# power.net
KiCad netlist of a schematic drawn in Altium Designer
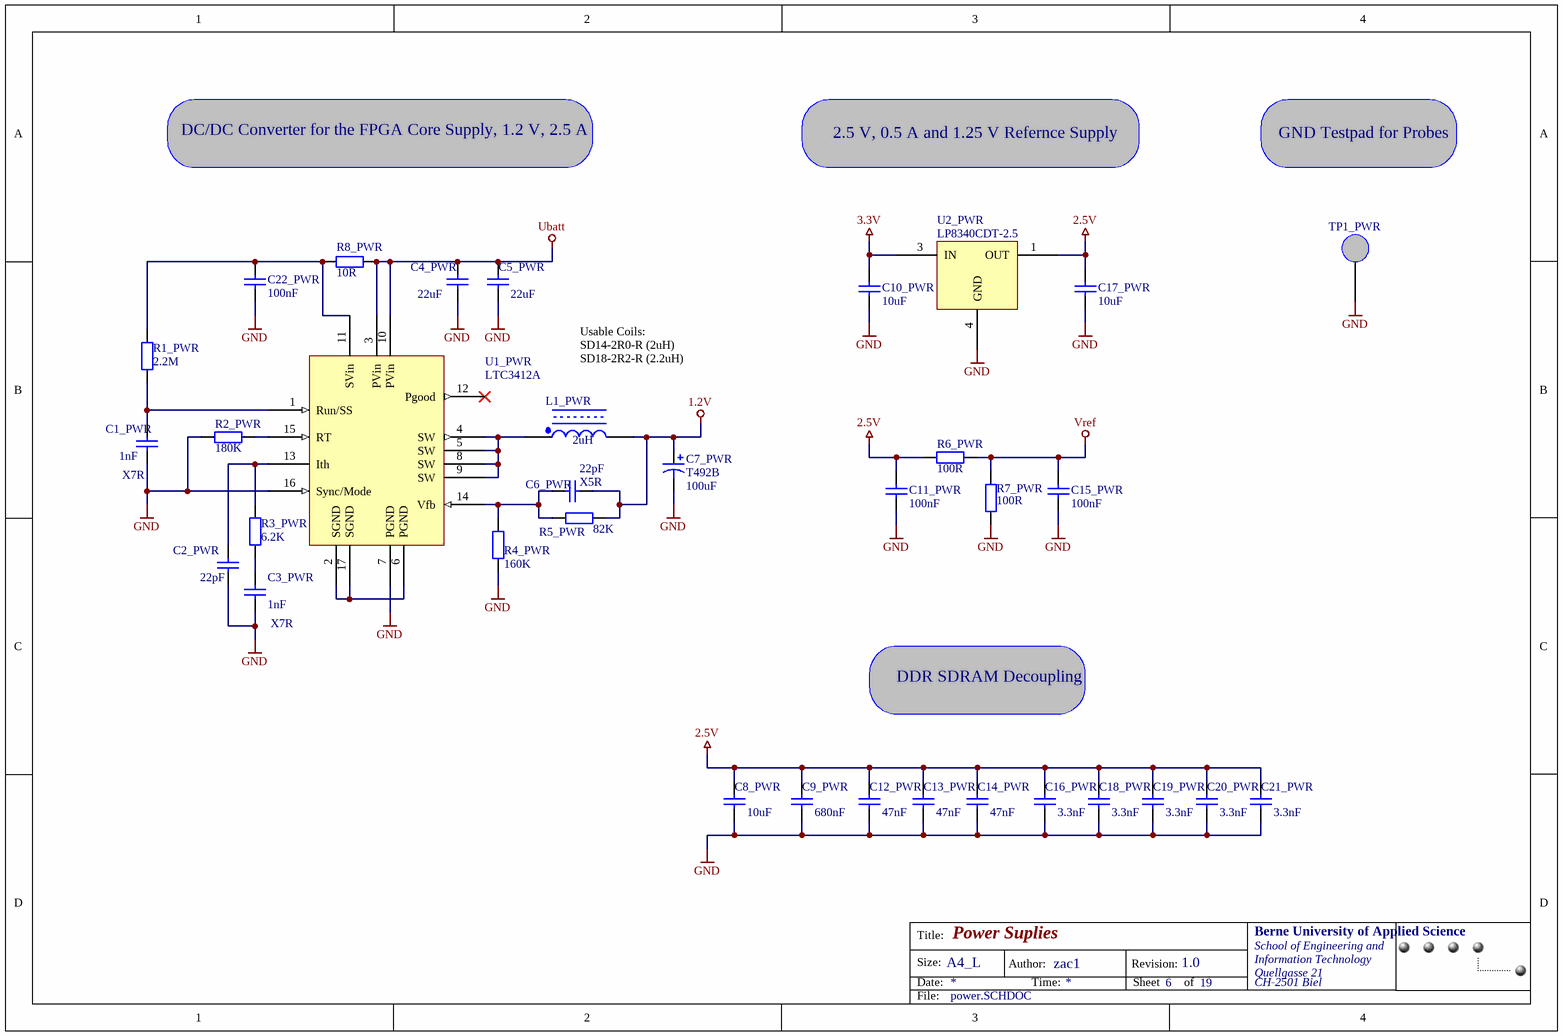
[diagram p0: power.SCHDOC]

(export (version "E")
  (design (tool "Eeschema 10.0.6"))
  (components
    (comp (ref "C1_PWR")
      (value "1nF")
      (footprint "0402")
      (description "Capacitor")
      (fields
        (field (name "MANUFACTURER") "PHYCOMP")
        (field (name "SPEC") "X7R")
        (field (name "PART NUMBER") "2238 587 15623")
        (field (name "PUBLISHER") "Altium Limited")
      )
      (libsource (lib "Miscellaneous Devices") (part "Cap"))
    )
    (comp (ref "C2_PWR")
      (value "22pF")
      (footprint "0402")
      (description "Capacitor")
      (fields
        (field (name "MANUFACTURER") "Murata")
        (field (name "PART NUMBER") "GRM1555C1H220JZ01D")
        (field (name "PUBLISHER") "Altium Limited")
      )
      (libsource (lib "Miscellaneous Devices") (part "Cap"))
    )
    (comp (ref "C3_PWR")
      (value "1nF")
      (footprint "0402")
      (description "Capacitor")
      (fields
        (field (name "MANUFACTURER") "PHYCOMP")
        (field (name "SPEC") "X7R")
        (field (name "PART NUMBER") "2238 587 15623")
        (field (name "PUBLISHER") "Altium Limited")
      )
      (libsource (lib "Miscellaneous Devices") (part "Cap"))
    )
    (comp (ref "C4_PWR")
      (value "22uF")
      (footprint "CC3225-1210")
      (description "Capacitor")
      (fields
        (field (name "MANUFACTURER") "Yuden")
        (field (name "PART NUMBER") "EMK325BJ226MM-T")
        (field (name "PUBLISHER") "Altium Limited")
      )
      (libsource (lib "Miscellaneous Devices") (part "Cap"))
    )
    (comp (ref "C5_PWR")
      (value "22uF")
      (footprint "1210")
      (description "Capacitor")
      (fields
        (field (name "MANUFACTURER") "Yuden")
        (field (name "PART NUMBER") "EMK325BJ226MM-T")
        (field (name "PUBLISHER") "Altium Limited")
      )
      (libsource (lib "Miscellaneous Devices") (part "Cap"))
    )
    (comp (ref "C6_PWR")
      (value "22pF")
      (footprint "0402")
      (description "Capacitor")
      (fields
        (field (name "MANUFACTURER") "Murata")
        (field (name "SPEC") "X5R")
        (field (name "PART NUMBER") "GRM1555C1H220JZ01D")
        (field (name "PUBLISHER") "Altium Limited")
      )
      (libsource (lib "Miscellaneous Devices") (part "Cap"))
    )
    (comp (ref "C7_PWR")
      (value "T492B")
      (footprint "B")
      (description "Solid Tantalum Chip Capacitor, T492 Series - CWR11 Style Per Mil-PRF-55365/8")
      (fields
        (field (name "ALTIUM_VALUE") "100uF")
        (field (name "MANUFACTURER") "AVX")
        (field (name "PART NUMBER") "TCJB107M004R0070")
        (field (name "PUBLISHER") "Altium Limited")
      )
      (libsource (lib "KEMET Chip Capacitor") (part "T492B"))
    )
    (comp (ref "C8_PWR")
      (value "10uF")
      (footprint "1206")
      (description "Capacitor")
      (fields
        (field (name "MANUFACTURER") "Murata")
        (field (name "PART NUMBER") "GRM31CR70J106KA01L")
        (field (name "PUBLISHER") "Altium Limited")
      )
      (libsource (lib "Miscellaneous Devices") (part "Cap"))
    )
    (comp (ref "C9_PWR")
      (value "680nF")
      (footprint "0805")
      (description "Capacitor")
      (fields
        (field (name "MANUFACTURER") "PHYCOMP")
        (field (name "PART NUMBER") "2238 240 15661")
        (field (name "PUBLISHER") "Altium Limited")
      )
      (libsource (lib "Miscellaneous Devices") (part "Cap"))
    )
    (comp (ref "C10_PWR")
      (value "10uF")
      (footprint "1206")
      (description "Capacitor")
      (fields
        (field (name "MANUFACTURER") "Murata")
        (field (name "PART NUMBER") "GRM31CR70J106KA01L")
        (field (name "PUBLISHER") "Altium Limited")
      )
      (libsource (lib "Miscellaneous Devices") (part "Cap"))
    )
    (comp (ref "C11_PWR")
      (value "100nF")
      (footprint "0402")
      (description "Capacitor")
      (fields
        (field (name "MANUFACTURER") "Murata")
        (field (name "PART NUMBER") "GRM155R71C104KA88D")
        (field (name "PUBLISHER") "Altium Limited")
      )
      (libsource (lib "Miscellaneous Devices") (part "Cap"))
    )
    (comp (ref "C12_PWR")
      (value "47nF")
      (footprint "0402")
      (description "Capacitor")
      (fields
        (field (name "MANUFACTURER") "PHYCOMP")
        (field (name "PART NUMBER") "2238 787 19845")
        (field (name "PUBLISHER") "Altium Limited")
      )
      (libsource (lib "Miscellaneous Devices") (part "Cap"))
    )
    (comp (ref "C13_PWR")
      (value "47nF")
      (footprint "0402")
      (description "Capacitor")
      (fields
        (field (name "MANUFACTURER") "PHYCOMP")
        (field (name "PART NUMBER") "2238 787 19845")
        (field (name "PUBLISHER") "Altium Limited")
      )
      (libsource (lib "Miscellaneous Devices") (part "Cap"))
    )
    (comp (ref "C14_PWR")
      (value "47nF")
      (footprint "0402")
      (description "Capacitor")
      (fields
        (field (name "MANUFACTURER") "PHYCOMP")
        (field (name "PART NUMBER") "2238 787 19845")
        (field (name "PUBLISHER") "Altium Limited")
      )
      (libsource (lib "Miscellaneous Devices") (part "Cap"))
    )
    (comp (ref "C15_PWR")
      (value "100nF")
      (footprint "0402")
      (description "Capacitor")
      (fields
        (field (name "MANUFACTURER") "Murata")
        (field (name "PART NUMBER") "GRM155R71C104KA88D")
        (field (name "PUBLISHER") "Altium Limited")
      )
      (libsource (lib "Miscellaneous Devices") (part "Cap"))
    )
    (comp (ref "C16_PWR")
      (value "3.3nF")
      (footprint "0402")
      (description "Capacitor")
      (fields
        (field (name "MANUFACTURER") "PHYCOMP")
        (field (name "PART NUMBER") "2238 587 15629")
        (field (name "PUBLISHER") "Altium Limited")
      )
      (libsource (lib "Miscellaneous Devices") (part "Cap"))
    )
    (comp (ref "C17_PWR")
      (value "10uF")
      (footprint "1206")
      (description "Capacitor")
      (fields
        (field (name "MANUFACTURER") "Murata")
        (field (name "PART NUMBER") "GRM31CR70J106KA01L")
        (field (name "PUBLISHER") "Altium Limited")
      )
      (libsource (lib "Miscellaneous Devices") (part "Cap"))
    )
    (comp (ref "C18_PWR")
      (value "3.3nF")
      (footprint "0402")
      (description "Capacitor")
      (fields
        (field (name "MANUFACTURER") "PHYCOMP")
        (field (name "PART NUMBER") "2238 587 15629")
        (field (name "PUBLISHER") "Altium Limited")
      )
      (libsource (lib "Miscellaneous Devices") (part "Cap"))
    )
    (comp (ref "C19_PWR")
      (value "3.3nF")
      (footprint "0402")
      (description "Capacitor")
      (fields
        (field (name "MANUFACTURER") "PHYCOMP")
        (field (name "PART NUMBER") "2238 587 15629")
        (field (name "PUBLISHER") "Altium Limited")
      )
      (libsource (lib "Miscellaneous Devices") (part "Cap"))
    )
    (comp (ref "C20_PWR")
      (value "3.3nF")
      (footprint "0402")
      (description "Capacitor")
      (fields
        (field (name "MANUFACTURER") "PHYCOMP")
        (field (name "PART NUMBER") "2238 587 15629")
        (field (name "PUBLISHER") "Altium Limited")
      )
      (libsource (lib "Miscellaneous Devices") (part "Cap"))
    )
    (comp (ref "C21_PWR")
      (value "3.3nF")
      (footprint "0402")
      (description "Capacitor")
      (fields
        (field (name "MANUFACTURER") "PHYCOMP")
        (field (name "PART NUMBER") "2238 587 15629")
        (field (name "PUBLISHER") "Altium Limited")
      )
      (libsource (lib "Miscellaneous Devices") (part "Cap"))
    )
    (comp (ref "C22_PWR")
      (value "100nF")
      (footprint "0402")
      (description "Capacitor")
      (fields
        (field (name "MANUFACTURER") "Murata")
        (field (name "PART NUMBER") "GRM155R71C104KA88D")
        (field (name "PUBLISHER") "Altium Limited")
      )
      (libsource (lib "") (part "Cap_1"))
    )
    (comp (ref "L1_PWR")
      (value "2uH")
      (footprint "coil-sd-serie")
      (description "SD Series Coils from Coiltronics")
      (fields (field (name "MANUFACTURER") "Cooper Bussmann") (field (name "PART NUMBER") "SD14-2R0-R"))
      (libsource (lib "gecko3-user") (part "COIL-SD-SERIE"))
    )
    (comp (ref "R1_PWR")
      (value "2.2M")
      (footprint "0402")
      (description "Resistor")
      (fields
        (field (name "MANUFACTURER") "PHYCOMP")
        (field (name "PART NUMBER") "232270672205")
        (field (name "PUBLISHER") "Altium Limited")
      )
      (libsource (lib "Miscellaneous Devices") (part "Res2"))
    )
    (comp (ref "R2_PWR")
      (value "180K")
      (footprint "0402")
      (description "Resistor")
      (fields
        (field (name "MANUFACTURER") "PHYCOMP")
        (field (name "PART NUMBER") "232270671804")
        (field (name "PUBLISHER") "Altium Limited")
      )
      (libsource (lib "") (part "Res2_1"))
    )
    (comp (ref "R3_PWR")
      (value "6.2K")
      (footprint "0603")
      (description "Resistor")
      (fields
        (field (name "MANUFACTURER") "Multicomp")
        (field (name "PART NUMBER") "MC 0.063W 0603 1% 6K2")
        (field (name "PUBLISHER") "Altium Limited")
      )
      (libsource (lib "") (part "Res2_2"))
    )
    (comp (ref "R4_PWR")
      (value "160K")
      (footprint "0603")
      (description "Resistor")
      (fields
        (field (name "MANUFACTURER") "Multicomp")
        (field (name "PART NUMBER") "MC 0.063W 0603 1% 160K")
        (field (name "PUBLISHER") "Altium Limited")
      )
      (libsource (lib "Miscellaneous Devices") (part "Res2"))
    )
    (comp (ref "R5_PWR")
      (value "82K")
      (footprint "0402")
      (description "Resistor")
      (fields
        (field (name "MANUFACTURER") "PHYCOMP")
        (field (name "PART NUMBER") "232270678203")
        (field (name "PUBLISHER") "Altium Limited")
      )
      (libsource (lib "") (part "Res2_1"))
    )
    (comp (ref "R6_PWR")
      (value "100R")
      (footprint "0402")
      (description "Resistor")
      (fields
        (field (name "MANUFACTURER") "PHYCOMP")
        (field (name "PART NUMBER") "232270671001")
        (field (name "PUBLISHER") "Altium Limited")
      )
      (libsource (lib "") (part "Res2_1"))
    )
    (comp (ref "R7_PWR")
      (value "100R")
      (footprint "0402")
      (description "Resistor")
      (fields
        (field (name "MANUFACTURER") "PHYCOMP")
        (field (name "PART NUMBER") "232270671001")
        (field (name "PUBLISHER") "Altium Limited")
      )
      (libsource (lib "Miscellaneous Devices") (part "Res2"))
    )
    (comp (ref "R8_PWR")
      (value "10R")
      (footprint "0402")
      (description "Resistor")
      (fields
        (field (name "MANUFACTURER") "TYCO ELECTRONICS")
        (field (name "PART NUMBER") "CRG0402J10R-10")
        (field (name "PUBLISHER") "Altium Limited")
      )
      (libsource (lib "") (part "Res2_1"))
    )
    (comp (ref "TP1_PWR")
      (value "TESTPAD-SMD")
      (footprint "TESTPAD-SMD")
      (description "Harwin SMD Testpad")
      (fields (field (name "MANUFACTURER") "HARWIN") (field (name "PART NUMBER") "S1751-46R"))
      (libsource (lib "gecko3-user") (part "TESTPAD-SMD"))
    )
    (comp (ref "U1_PWR")
      (value "LTC3412A")
      (footprint "QFN16")
      (description "3 A, 4 MHz, Step-Down Regulator")
      (fields (field (name "MANUFACTURER") "Linear") (field (name "PART NUMBER") "LTC3412AEUF#PBF"))
      (libsource (lib "gecko3-user") (part "LTC3412A"))
    )
    (comp (ref "U2_PWR")
      (value "LP8340CDT-2.5")
      (footprint "TO-252")
      (description "Low Dropout, Low IQ, 1.0A CMOS Linear Regulator")
      (fields (field (name "MANUFACTURER") "National") (field (name "Comment") "LP8340CDT"))
      (libsource (lib "gecko3-user") (part "LP8340CDT"))
    )
  )
  (nets
    (net (code "1") (name "1.2V") (class "Default")
      (node (ref "C6_PWR") (pin "1") (pinfunction "1_1") (pintype "passive"))
      (node (ref "C7_PWR") (pin "1") (pinfunction "1_1") (pintype "passive"))
      (node (ref "L1_PWR") (pin "2") (pinfunction "2_2") (pintype "passive"))
      (node (ref "R5_PWR") (pin "1") (pinfunction "1_1") (pintype "passive"))
    )
    (net (code "2") (name "2.5V") (class "Default")
      (node (ref "C11_PWR") (pin "2") (pinfunction "2_2") (pintype "passive"))
      (node (ref "C12_PWR") (pin "1") (pinfunction "1_1") (pintype "passive"))
      (node (ref "C13_PWR") (pin "1") (pinfunction "1_1") (pintype "passive"))
      (node (ref "C14_PWR") (pin "1") (pinfunction "1_1") (pintype "passive"))
      (node (ref "C16_PWR") (pin "1") (pinfunction "1_1") (pintype "passive"))
      (node (ref "C17_PWR") (pin "2") (pinfunction "2_2") (pintype "passive"))
      (node (ref "C18_PWR") (pin "1") (pinfunction "1_1") (pintype "passive"))
      (node (ref "C19_PWR") (pin "1") (pinfunction "1_1") (pintype "passive"))
      (node (ref "C20_PWR") (pin "1") (pinfunction "1_1") (pintype "passive"))
      (node (ref "C21_PWR") (pin "1") (pinfunction "1_1") (pintype "passive"))
      (node (ref "C8_PWR") (pin "1") (pinfunction "1_1") (pintype "passive"))
      (node (ref "C9_PWR") (pin "1") (pinfunction "1_1") (pintype "passive"))
      (node (ref "R6_PWR") (pin "2") (pinfunction "2_2") (pintype "passive"))
      (node (ref "U2_PWR") (pin "1") (pinfunction "OUT_1") (pintype "power_in"))
    )
    (net (code "3") (name "3.3V") (class "Default")
      (node (ref "C10_PWR") (pin "2") (pinfunction "2_2") (pintype "passive"))
      (node (ref "U2_PWR") (pin "3") (pinfunction "IN_3") (pintype "power_in"))
    )
    (net (code "4") (name "GND") (class "Default")
      (node (ref "C10_PWR") (pin "1") (pinfunction "1_1") (pintype "passive"))
      (node (ref "C11_PWR") (pin "1") (pinfunction "1_1") (pintype "passive"))
      (node (ref "C12_PWR") (pin "2") (pinfunction "2_2") (pintype "passive"))
      (node (ref "C13_PWR") (pin "2") (pinfunction "2_2") (pintype "passive"))
      (node (ref "C14_PWR") (pin "2") (pinfunction "2_2") (pintype "passive"))
      (node (ref "C15_PWR") (pin "1") (pinfunction "1_1") (pintype "passive"))
      (node (ref "C16_PWR") (pin "2") (pinfunction "2_2") (pintype "passive"))
      (node (ref "C17_PWR") (pin "1") (pinfunction "1_1") (pintype "passive"))
      (node (ref "C18_PWR") (pin "2") (pinfunction "2_2") (pintype "passive"))
      (node (ref "C19_PWR") (pin "2") (pinfunction "2_2") (pintype "passive"))
      (node (ref "C1_PWR") (pin "1") (pinfunction "1_1") (pintype "passive"))
      (node (ref "C20_PWR") (pin "2") (pinfunction "2_2") (pintype "passive"))
      (node (ref "C21_PWR") (pin "2") (pinfunction "2_2") (pintype "passive"))
      (node (ref "C22_PWR") (pin "2") (pinfunction "2_2") (pintype "passive"))
      (node (ref "C2_PWR") (pin "1") (pinfunction "1_1") (pintype "passive"))
      (node (ref "C3_PWR") (pin "1") (pinfunction "1_1") (pintype "passive"))
      (node (ref "C4_PWR") (pin "1") (pinfunction "1_1") (pintype "passive"))
      (node (ref "C5_PWR") (pin "1") (pinfunction "1_1") (pintype "passive"))
      (node (ref "C7_PWR") (pin "2") (pinfunction "2_2") (pintype "passive"))
      (node (ref "C8_PWR") (pin "2") (pinfunction "2_2") (pintype "passive"))
      (node (ref "C9_PWR") (pin "2") (pinfunction "2_2") (pintype "passive"))
      (node (ref "R2_PWR") (pin "2") (pinfunction "2_2") (pintype "passive"))
      (node (ref "R4_PWR") (pin "1") (pinfunction "1_1") (pintype "passive"))
      (node (ref "R7_PWR") (pin "1") (pinfunction "1_1") (pintype "passive"))
      (node (ref "TP1_PWR") (pin "1") (pintype "passive"))
      (node (ref "U1_PWR") (pin "16") (pinfunction "Sync/Mode_16") (pintype "input"))
      (node (ref "U1_PWR") (pin "7") (pinfunction "PGND_7") (pintype "power_in"))
      (node (ref "U2_PWR") (pin "4") (pinfunction "GND_4") (pintype "power_in"))
    )
    (net (code "5") (name "Net-(C3_PWR-Pad2)") (class "Default")
      (node (ref "C3_PWR") (pin "2") (pinfunction "2_2") (pintype "passive"))
      (node (ref "R3_PWR") (pin "2") (pinfunction "2_2") (pintype "passive"))
    )
    (net (code "6") (name "Net-(L1_PWR-Pad1)") (class "Default")
      (node (ref "L1_PWR") (pin "1") (pinfunction "1_1") (pintype "passive"))
      (node (ref "U1_PWR") (pin "4") (pinfunction "SW_4") (pintype "output"))
      (node (ref "U1_PWR") (pin "5") (pinfunction "SW_5") (pintype "passive"))
      (node (ref "U1_PWR") (pin "8") (pinfunction "SW_8") (pintype "passive"))
      (node (ref "U1_PWR") (pin "9") (pinfunction "SW_9") (pintype "passive"))
    )
    (net (code "7") (name "Net-(U1_PWR-Ith)") (class "Default")
      (node (ref "C2_PWR") (pin "2") (pinfunction "2_2") (pintype "passive"))
      (node (ref "R3_PWR") (pin "1") (pinfunction "1_1") (pintype "passive"))
      (node (ref "U1_PWR") (pin "13") (pinfunction "Ith_13") (pintype "passive"))
    )
    (net (code "8") (name "Net-(U1_PWR-PGND-Pad6)") (class "Default")
      (node (ref "U1_PWR") (pin "17") (pinfunction "SGND_17") (pintype "power_in"))
      (node (ref "U1_PWR") (pin "2") (pinfunction "SGND_2") (pintype "power_in"))
      (node (ref "U1_PWR") (pin "6") (pinfunction "PGND_6") (pintype "power_in"))
    )
    (net (code "9") (name "Net-(U1_PWR-RT)") (class "Default")
      (node (ref "R2_PWR") (pin "1") (pinfunction "1_1") (pintype "passive"))
      (node (ref "U1_PWR") (pin "15") (pinfunction "RT_15") (pintype "input"))
    )
    (net (code "10") (name "Net-(U1_PWR-Run{slash}SS)") (class "Default")
      (node (ref "C1_PWR") (pin "2") (pinfunction "2_2") (pintype "passive"))
      (node (ref "R1_PWR") (pin "1") (pinfunction "1_1") (pintype "passive"))
      (node (ref "U1_PWR") (pin "1") (pinfunction "Run/SS_1") (pintype "input"))
    )
    (net (code "11") (name "Net-(U1_PWR-SVin)") (class "Default")
      (node (ref "C22_PWR") (pin "1") (pinfunction "1_1") (pintype "passive"))
      (node (ref "R1_PWR") (pin "2") (pinfunction "2_2") (pintype "passive"))
      (node (ref "R8_PWR") (pin "2") (pinfunction "2_2") (pintype "passive"))
      (node (ref "U1_PWR") (pin "11") (pinfunction "SVin_11") (pintype "power_in"))
    )
    (net (code "12") (name "Net-(U1_PWR-Vfb)") (class "Default")
      (node (ref "C6_PWR") (pin "2") (pinfunction "2_2") (pintype "passive"))
      (node (ref "R4_PWR") (pin "2") (pinfunction "2_2") (pintype "passive"))
      (node (ref "R5_PWR") (pin "2") (pinfunction "2_2") (pintype "passive"))
      (node (ref "U1_PWR") (pin "14") (pinfunction "Vfb_14") (pintype "input"))
    )
    (net (code "13") (name "Ubatt") (class "Default")
      (node (ref "C4_PWR") (pin "2") (pinfunction "2_2") (pintype "passive"))
      (node (ref "C5_PWR") (pin "2") (pinfunction "2_2") (pintype "passive"))
      (node (ref "R8_PWR") (pin "1") (pinfunction "1_1") (pintype "passive"))
      (node (ref "U1_PWR") (pin "10") (pinfunction "PVin_10") (pintype "power_in"))
      (node (ref "U1_PWR") (pin "3") (pinfunction "PVin_3") (pintype "power_in"))
    )
    (net (code "14") (name "Vref") (class "Default")
      (node (ref "C15_PWR") (pin "2") (pinfunction "2_2") (pintype "passive"))
      (node (ref "R6_PWR") (pin "1") (pinfunction "1_1") (pintype "passive"))
      (node (ref "R7_PWR") (pin "2") (pinfunction "2_2") (pintype "passive"))
    )
    (net (code "15") (name "unconnected-(U1_PWR-Pgood-Pad12)") (class "Default")
      (node (ref "U1_PWR") (pin "12") (pinfunction "Pgood_12") (pintype "output+no_connect"))
    )
  )
)
